# ECE411_Haptic_Compass.net
KiCad netlist of a schematic drawn in EAGLE
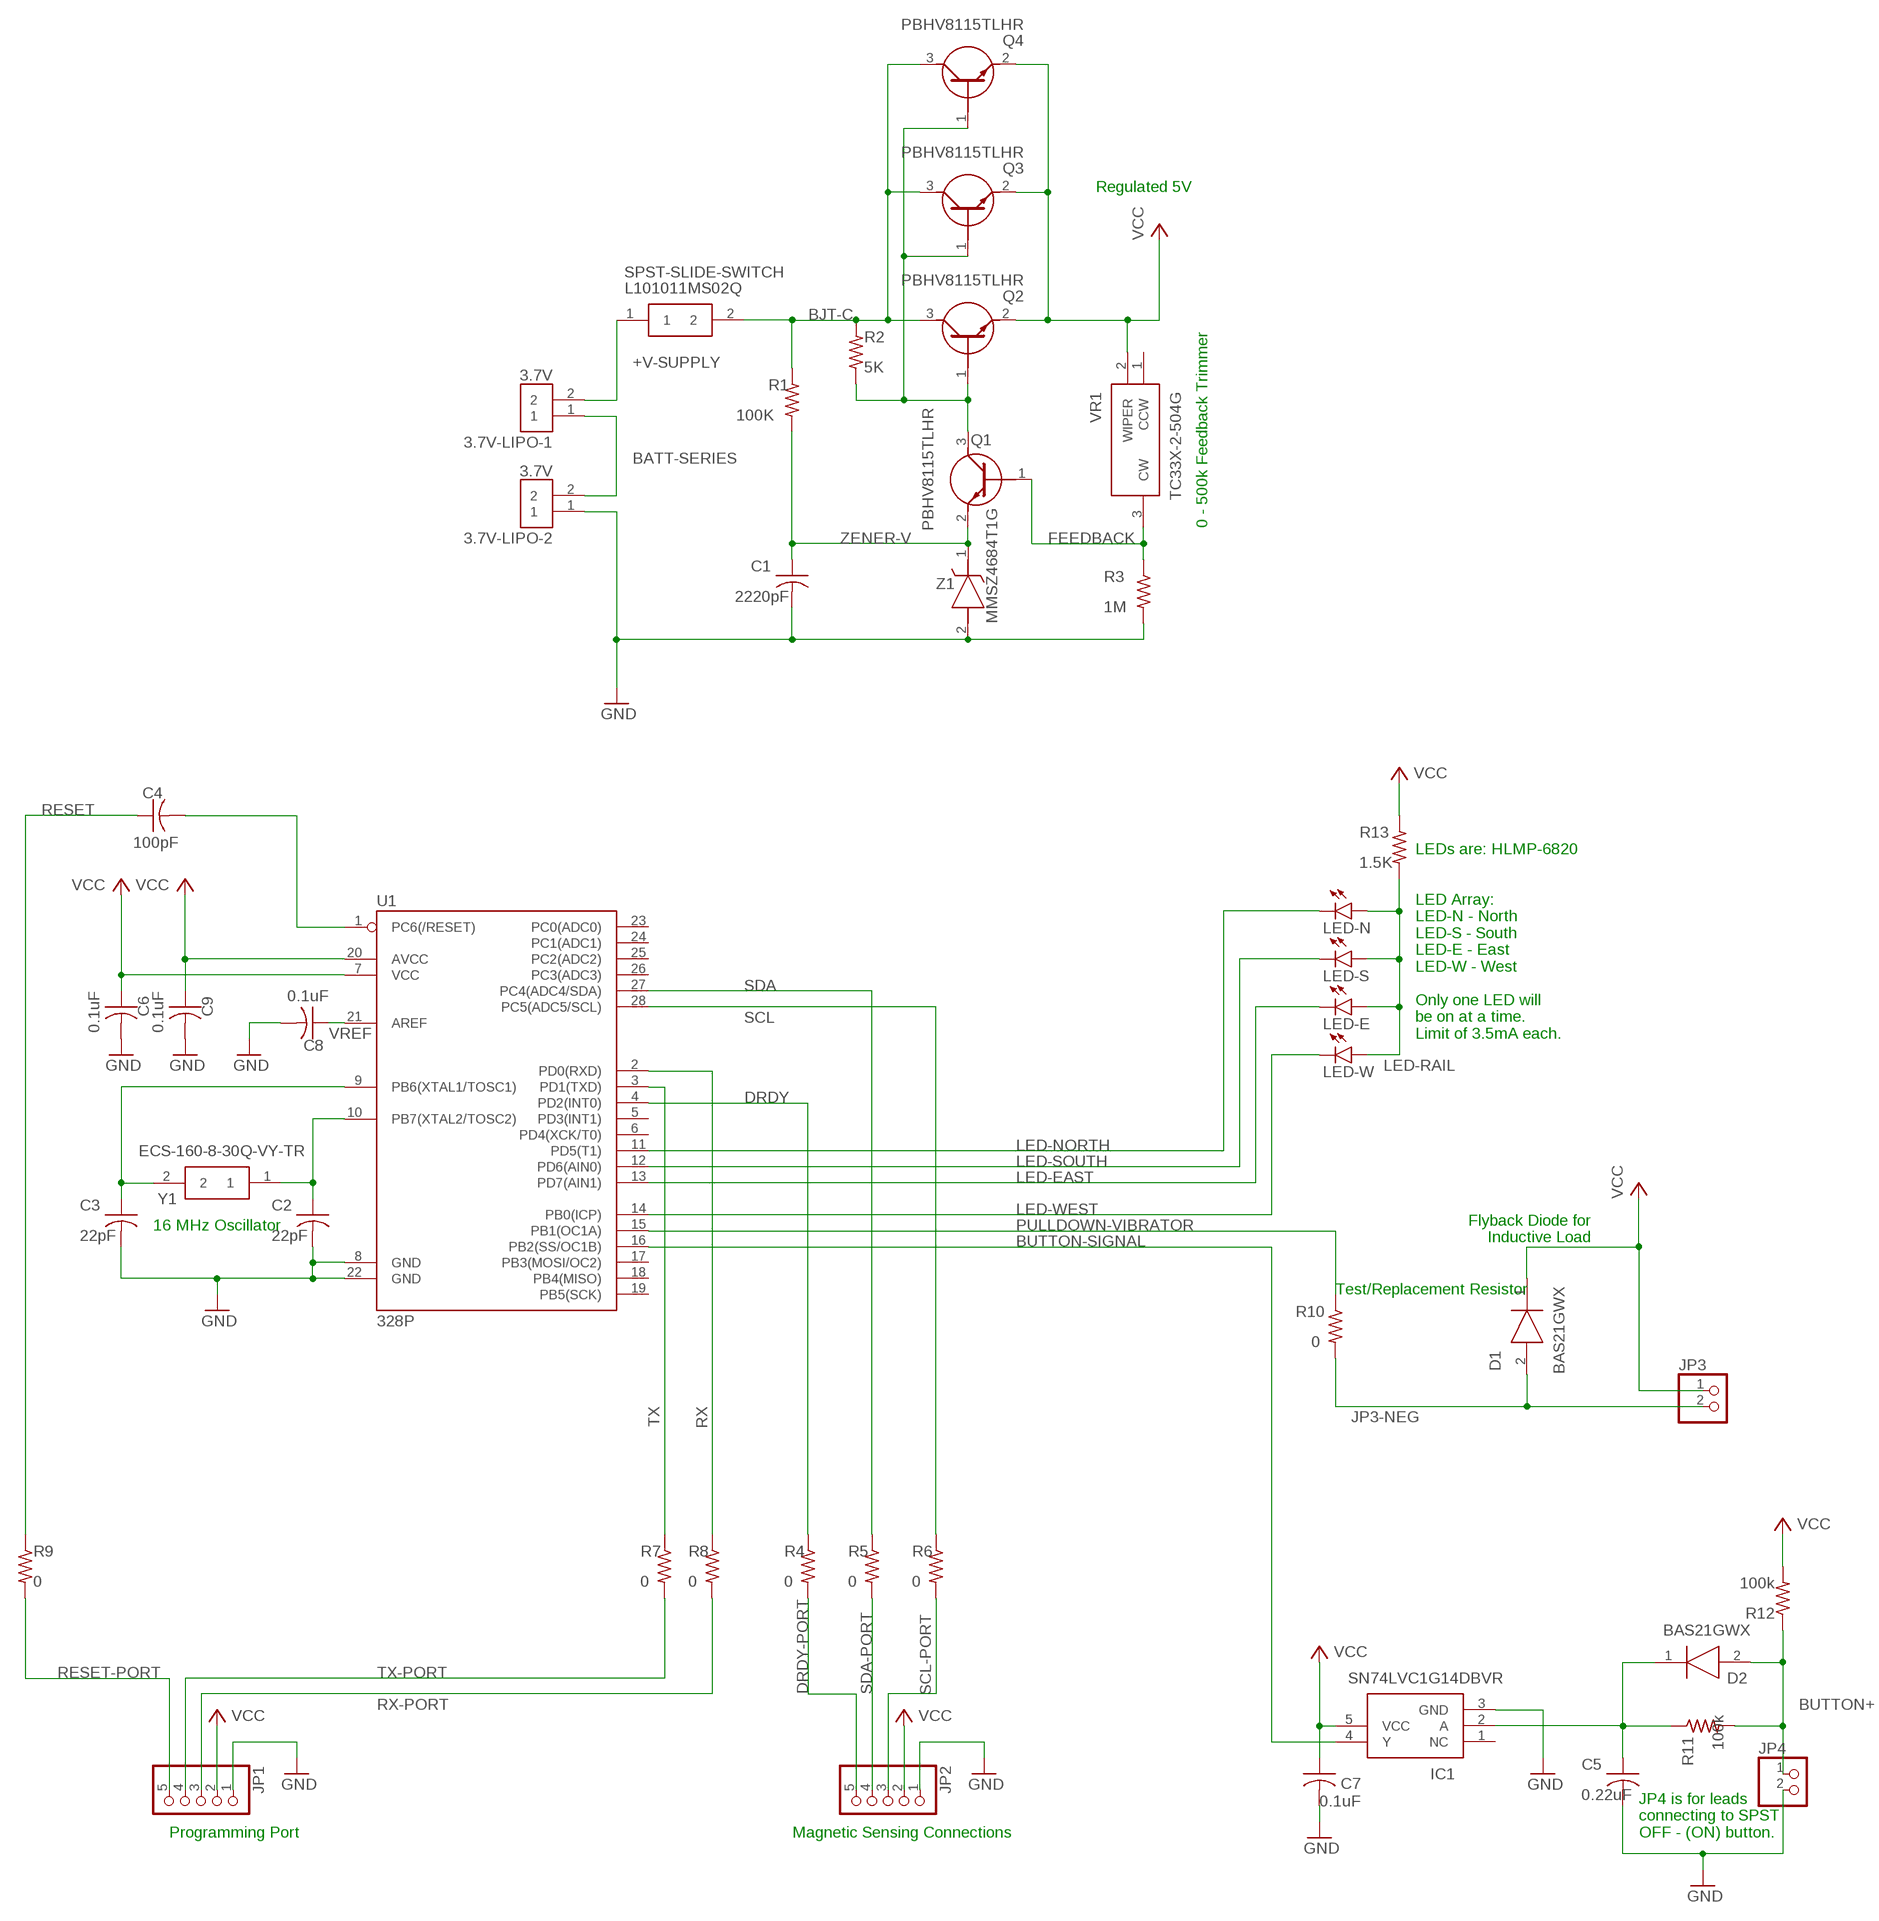
[diagram p0: schematic, sheet 1]

(export (version "E")
  (design (tool "Eeschema 10.0.6"))
  (components
    (comp (ref "3.7V-LIPO-1")
      (value "3.7V")
      (footprint "eagle-import:JST_S2B-PH-K-S(LF)(SN)")
      (fields
        (field (name "DIGI-KEY_PART_NUMBER") "455-1719-ND")
        (field (name "MF") "JST Sales")
        (field (name "MP") "S2B-PH-K-S_LF__SN_")
      )
      (libsource (lib "eagle-import") (part "S2B-PH-K-S(LF)(SN)"))
    )
    (comp (ref "3.7V-LIPO-2")
      (value "3.7V")
      (footprint "eagle-import:JST_S2B-PH-K-S(LF)(SN)")
      (fields
        (field (name "DIGI-KEY_PART_NUMBER") "455-1719-ND")
        (field (name "MF") "JST Sales")
        (field (name "MP") "S2B-PH-K-S_LF__SN_")
      )
      (libsource (lib "eagle-import") (part "S2B-PH-K-S(LF)(SN)"))
    )
    (comp (ref "C1")
      (value "2220pF")
      (footprint "eagle-import:C0805")
      (libsource (lib "eagle-import") (part "C-USC0805"))
    )
    (comp (ref "C2")
      (value "22pF")
      (footprint "eagle-import:C0805")
      (libsource (lib "eagle-import") (part "C-USC0805"))
    )
    (comp (ref "C3")
      (value "22pF")
      (footprint "eagle-import:C0805")
      (libsource (lib "eagle-import") (part "C-USC0805"))
    )
    (comp (ref "C4")
      (value "100pF")
      (footprint "eagle-import:C0805")
      (libsource (lib "eagle-import") (part "C-USC0805"))
    )
    (comp (ref "C5")
      (value "0.22uF")
      (footprint "eagle-import:C0805")
      (libsource (lib "eagle-import") (part "C-USC0805"))
    )
    (comp (ref "C6")
      (value "0.1uF")
      (footprint "eagle-import:C0805")
      (libsource (lib "eagle-import") (part "C-USC0805"))
    )
    (comp (ref "C7")
      (value "0.1uF")
      (footprint "eagle-import:C0805")
      (libsource (lib "eagle-import") (part "C-USC0805"))
    )
    (comp (ref "C8")
      (value "0.1uF")
      (footprint "eagle-import:C0805")
      (libsource (lib "eagle-import") (part "C-USC0805"))
    )
    (comp (ref "C9")
      (value "0.1uF")
      (footprint "eagle-import:C0805")
      (libsource (lib "eagle-import") (part "C-USC0805"))
    )
    (comp (ref "D1")
      (value "BAS21GWX")
      (footprint "eagle-import:SOD3616X130N")
      (fields (field (name "MOUSER_PART_NUMBER") "841-BAS21GWX"))
      (libsource (lib "eagle-import") (part "BAS21GWX"))
    )
    (comp (ref "D2")
      (value "BAS21GWX")
      (footprint "eagle-import:SOD3616X130N")
      (fields (field (name "MOUSER_PART_NUMBER") "841-BAS21GWX"))
      (libsource (lib "eagle-import") (part "BAS21GWX"))
    )
    (comp (ref "IC1")
      (value "SN74LVC1G14DBVR")
      (footprint "eagle-import:SOT95P280X145-5N")
      (fields (field (name "MOUSER_PART_NUMBER") "595-SN74LVC1G14DBVR"))
      (libsource (lib "eagle-import") (part "SN74LVC1G14DBVR"))
    )
    (comp (ref "JP1")
      (value "PINHD-1X5")
      (footprint "eagle-import:1X05")
      (libsource (lib "eagle-import") (part "PINHD-1X5"))
    )
    (comp (ref "JP2")
      (value "PINHD-1X5")
      (footprint "eagle-import:1X05")
      (libsource (lib "eagle-import") (part "PINHD-1X5"))
    )
    (comp (ref "JP3")
      (value "PINHD-1X2")
      (footprint "eagle-import:1X02")
      (libsource (lib "eagle-import") (part "PINHD-1X2"))
    )
    (comp (ref "JP4")
      (value "PINHD-1X2")
      (footprint "eagle-import:1X02")
      (libsource (lib "eagle-import") (part "PINHD-1X2"))
    )
    (comp (ref "LED-E")
      (value "LED5MM")
      (footprint "eagle-import:LED5MM")
      (libsource (lib "eagle-import") (part "LED5MM"))
    )
    (comp (ref "LED-N")
      (value "LED5MM")
      (footprint "eagle-import:LED5MM")
      (libsource (lib "eagle-import") (part "LED5MM"))
    )
    (comp (ref "LED-S")
      (value "LED5MM")
      (footprint "eagle-import:LED5MM")
      (libsource (lib "eagle-import") (part "LED5MM"))
    )
    (comp (ref "LED-W")
      (value "LED5MM")
      (footprint "eagle-import:LED5MM")
      (libsource (lib "eagle-import") (part "LED5MM"))
    )
    (comp (ref "Q1")
      (value "PBHV8115TLHR")
      (footprint "eagle-import:SOT95P230X110-3N")
      (fields (field (name "MOUSER_PART_NUMBER") "771-PBHV8115TLHR"))
      (libsource (lib "eagle-import") (part "PBHV8115TLHR"))
    )
    (comp (ref "Q2")
      (value "PBHV8115TLHR")
      (footprint "eagle-import:SOT95P230X110-3N")
      (fields (field (name "MOUSER_PART_NUMBER") "771-PBHV8115TLHR"))
      (libsource (lib "eagle-import") (part "PBHV8115TLHR"))
    )
    (comp (ref "Q3")
      (value "PBHV8115TLHR")
      (footprint "eagle-import:SOT95P230X110-3N")
      (fields (field (name "MOUSER_PART_NUMBER") "771-PBHV8115TLHR"))
      (libsource (lib "eagle-import") (part "PBHV8115TLHR"))
    )
    (comp (ref "Q4")
      (value "PBHV8115TLHR")
      (footprint "eagle-import:SOT95P230X110-3N")
      (fields (field (name "MOUSER_PART_NUMBER") "771-PBHV8115TLHR"))
      (libsource (lib "eagle-import") (part "PBHV8115TLHR"))
    )
    (comp (ref "R1")
      (value "100K")
      (footprint "eagle-import:R0805")
      (libsource (lib "eagle-import") (part "R-US_R0805"))
    )
    (comp (ref "R2")
      (value "5K")
      (footprint "eagle-import:R0805")
      (libsource (lib "eagle-import") (part "R-US_R0805"))
    )
    (comp (ref "R3")
      (value "1M")
      (footprint "eagle-import:R0805")
      (libsource (lib "eagle-import") (part "R-US_R0805"))
    )
    (comp (ref "R4")
      (value "0")
      (footprint "eagle-import:R0805")
      (libsource (lib "eagle-import") (part "R-US_R0805"))
    )
    (comp (ref "R5")
      (value "0")
      (footprint "eagle-import:R0805")
      (libsource (lib "eagle-import") (part "R-US_R0805"))
    )
    (comp (ref "R6")
      (value "0")
      (footprint "eagle-import:R0805")
      (libsource (lib "eagle-import") (part "R-US_R0805"))
    )
    (comp (ref "R7")
      (value "0")
      (footprint "eagle-import:R0805")
      (libsource (lib "eagle-import") (part "R-US_R0805"))
    )
    (comp (ref "R8")
      (value "0")
      (footprint "eagle-import:R0805")
      (libsource (lib "eagle-import") (part "R-US_R0805"))
    )
    (comp (ref "R9")
      (value "0")
      (footprint "eagle-import:R0805")
      (libsource (lib "eagle-import") (part "R-US_R0805"))
    )
    (comp (ref "R10")
      (value "0")
      (footprint "eagle-import:R0805")
      (libsource (lib "eagle-import") (part "R-US_R0805"))
    )
    (comp (ref "R11")
      (value "100k")
      (footprint "eagle-import:R0805")
      (libsource (lib "eagle-import") (part "R-US_R0805"))
    )
    (comp (ref "R12")
      (value "100k")
      (footprint "eagle-import:R0805")
      (libsource (lib "eagle-import") (part "R-US_R0805"))
    )
    (comp (ref "R13")
      (value "1.5K")
      (footprint "eagle-import:R0805")
      (libsource (lib "eagle-import") (part "R-US_R0805"))
    )
    (comp (ref "SPST-SLIDE-SWITCH")
      (value "L101011MS02Q")
      (footprint "eagle-import:CKC5106-ND")
      (fields (field (name "MOUSER_PART_NUMBER") "611-L101011MS02Q"))
      (libsource (lib "eagle-import") (part "L101011MS02Q"))
    )
    (comp (ref "U1")
      (value "328P")
      (footprint "eagle-import:DIP28")
      (libsource (lib "eagle-import") (part "ATMEGA328P_PDIP"))
    )
    (comp (ref "VR1")
      (value "TC33X-2-504G")
      (footprint "eagle-import:TC33X-2_1")
      (fields (field (name "MOUSER_PART_NUMBER") "652-TC33X-2-504G"))
      (libsource (lib "eagle-import") (part "TC33X-2-504G"))
    )
    (comp (ref "Y1")
      (value "ECS-160-8-30Q-VY-TR")
      (footprint "eagle-import:ECS80830QVSTR")
      (fields (field (name "MOUSER_PART_NUMBER") "520-160-8-30Q-VYT"))
      (libsource (lib "eagle-import") (part "ECS-160-8-30Q-VY-TR"))
    )
    (comp (ref "Z1")
      (value "MMSZ4684T1G")
      (footprint "eagle-import:SOD3716X135N")
      (fields (field (name "MOUSER_PART_NUMBER") "863-MMSZ4684T1G"))
      (libsource (lib "eagle-import") (part "MMSZ4684T1G"))
    )
  )
  (nets
    (net (code "1") (name "/+V-SUPPLY") (class "Default")
      (node (ref "3.7V-LIPO-1") (pin "2") (pinfunction "2_2") (pintype "passive"))
      (node (ref "SPST-SLIDE-SWITCH") (pin "1") (pinfunction "1_1") (pintype "bidirectional"))
    )
    (net (code "2") (name "/BATT-SERIES") (class "Default")
      (node (ref "3.7V-LIPO-1") (pin "1") (pinfunction "1_1") (pintype "passive"))
      (node (ref "3.7V-LIPO-2") (pin "2") (pinfunction "2_2") (pintype "passive"))
    )
    (net (code "3") (name "/BJT-C") (class "Default")
      (node (ref "Q2") (pin "3") (pinfunction "C_3") (pintype "bidirectional"))
      (node (ref "Q3") (pin "3") (pinfunction "C_3") (pintype "bidirectional"))
      (node (ref "Q4") (pin "3") (pinfunction "C_3") (pintype "bidirectional"))
      (node (ref "R1") (pin "1") (pinfunction "1_1") (pintype "passive"))
      (node (ref "R2") (pin "1") (pinfunction "1_1") (pintype "passive"))
      (node (ref "SPST-SLIDE-SWITCH") (pin "2") (pinfunction "2_2") (pintype "bidirectional"))
    )
    (net (code "4") (name "/BUTTON+") (class "Default")
      (node (ref "D2") (pin "2") (pinfunction "A_2") (pintype "bidirectional"))
      (node (ref "JP4") (pin "1") (pinfunction "1_1") (pintype "passive"))
      (node (ref "R11") (pin "2") (pinfunction "2_2") (pintype "passive"))
      (node (ref "R12") (pin "1") (pinfunction "1_1") (pintype "passive"))
    )
    (net (code "5") (name "/BUTTON-SIGNAL") (class "Default")
      (node (ref "IC1") (pin "4") (pinfunction "Y_4") (pintype "bidirectional"))
      (node (ref "U1") (pin "16") (pinfunction "PB2(SS/OC1B)_16") (pintype "bidirectional"))
    )
    (net (code "6") (name "/DRDY") (class "Default")
      (node (ref "R4") (pin "1") (pinfunction "1_1") (pintype "passive"))
      (node (ref "U1") (pin "4") (pinfunction "PD2(INT0)_4") (pintype "bidirectional"))
    )
    (net (code "7") (name "/DRDY-PORT") (class "Default")
      (node (ref "JP2") (pin "5") (pinfunction "5_5") (pintype "passive"))
      (node (ref "R4") (pin "2") (pinfunction "2_2") (pintype "passive"))
    )
    (net (code "8") (name "/FEEDBACK") (class "Default")
      (node (ref "Q1") (pin "1") (pinfunction "B_1") (pintype "bidirectional"))
      (node (ref "R3") (pin "1") (pinfunction "1_1") (pintype "passive"))
      (node (ref "VR1") (pin "3") (pinfunction "CW_3") (pintype "bidirectional"))
    )
    (net (code "9") (name "/JP3-NEG") (class "Default")
      (node (ref "D1") (pin "2") (pinfunction "A_2") (pintype "bidirectional"))
      (node (ref "JP3") (pin "2") (pinfunction "2_2") (pintype "passive"))
      (node (ref "R10") (pin "2") (pinfunction "2_2") (pintype "passive"))
    )
    (net (code "10") (name "/LED-EAST") (class "Default")
      (node (ref "LED-E") (pin "K") (pinfunction "C_K") (pintype "passive"))
      (node (ref "U1") (pin "13") (pinfunction "PD7(AIN1)_13") (pintype "bidirectional"))
    )
    (net (code "11") (name "/LED-NORTH") (class "Default")
      (node (ref "LED-N") (pin "K") (pinfunction "C_K") (pintype "passive"))
      (node (ref "U1") (pin "11") (pinfunction "PD5(T1)_11") (pintype "bidirectional"))
    )
    (net (code "12") (name "/LED-RAIL") (class "Default")
      (node (ref "LED-E") (pin "A") (pinfunction "A_A") (pintype "passive"))
      (node (ref "LED-N") (pin "A") (pinfunction "A_A") (pintype "passive"))
      (node (ref "LED-S") (pin "A") (pinfunction "A_A") (pintype "passive"))
      (node (ref "LED-W") (pin "A") (pinfunction "A_A") (pintype "passive"))
      (node (ref "R13") (pin "2") (pinfunction "2_2") (pintype "passive"))
    )
    (net (code "13") (name "/LED-SOUTH") (class "Default")
      (node (ref "LED-S") (pin "K") (pinfunction "C_K") (pintype "passive"))
      (node (ref "U1") (pin "12") (pinfunction "PD6(AIN0)_12") (pintype "bidirectional"))
    )
    (net (code "14") (name "/LED-WEST") (class "Default")
      (node (ref "LED-W") (pin "K") (pinfunction "C_K") (pintype "passive"))
      (node (ref "U1") (pin "14") (pinfunction "PB0(ICP)_14") (pintype "bidirectional"))
    )
    (net (code "15") (name "/PULLDOWN-VIBRATOR") (class "Default")
      (node (ref "R10") (pin "1") (pinfunction "1_1") (pintype "passive"))
      (node (ref "U1") (pin "15") (pinfunction "PB1(OC1A)_15") (pintype "bidirectional"))
    )
    (net (code "16") (name "/RESET") (class "Default")
      (node (ref "C4") (pin "1") (pinfunction "1_1") (pintype "passive"))
      (node (ref "R9") (pin "1") (pinfunction "1_1") (pintype "passive"))
    )
    (net (code "17") (name "/RESET-PORT") (class "Default")
      (node (ref "JP1") (pin "5") (pinfunction "5_5") (pintype "passive"))
      (node (ref "R9") (pin "2") (pinfunction "2_2") (pintype "passive"))
    )
    (net (code "18") (name "/RX") (class "Default")
      (node (ref "R8") (pin "1") (pinfunction "1_1") (pintype "passive"))
      (node (ref "U1") (pin "2") (pinfunction "PD0(RXD)_2") (pintype "bidirectional"))
    )
    (net (code "19") (name "/RX-PORT") (class "Default")
      (node (ref "JP1") (pin "3") (pinfunction "3_3") (pintype "passive"))
      (node (ref "R8") (pin "2") (pinfunction "2_2") (pintype "passive"))
    )
    (net (code "20") (name "/SCL") (class "Default")
      (node (ref "R6") (pin "1") (pinfunction "1_1") (pintype "passive"))
      (node (ref "U1") (pin "28") (pinfunction "PC5(ADC5/SCL)_28") (pintype "bidirectional"))
    )
    (net (code "21") (name "/SCL-PORT") (class "Default")
      (node (ref "JP2") (pin "3") (pinfunction "3_3") (pintype "passive"))
      (node (ref "R6") (pin "2") (pinfunction "2_2") (pintype "passive"))
    )
    (net (code "22") (name "/SDA") (class "Default")
      (node (ref "R5") (pin "1") (pinfunction "1_1") (pintype "passive"))
      (node (ref "U1") (pin "27") (pinfunction "PC4(ADC4/SDA)_27") (pintype "bidirectional"))
    )
    (net (code "23") (name "/SDA-PORT") (class "Default")
      (node (ref "JP2") (pin "4") (pinfunction "4_4") (pintype "passive"))
      (node (ref "R5") (pin "2") (pinfunction "2_2") (pintype "passive"))
    )
    (net (code "24") (name "/TX") (class "Default")
      (node (ref "R7") (pin "1") (pinfunction "1_1") (pintype "passive"))
      (node (ref "U1") (pin "3") (pinfunction "PD1(TXD)_3") (pintype "bidirectional"))
    )
    (net (code "25") (name "/TX-PORT") (class "Default")
      (node (ref "JP1") (pin "4") (pinfunction "4_4") (pintype "passive"))
      (node (ref "R7") (pin "2") (pinfunction "2_2") (pintype "passive"))
    )
    (net (code "26") (name "/VREF") (class "Default")
      (node (ref "C8") (pin "1") (pinfunction "1_1") (pintype "passive"))
      (node (ref "U1") (pin "21") (pinfunction "AREF_21") (pintype "bidirectional"))
    )
    (net (code "27") (name "/ZENER-V") (class "Default")
      (node (ref "C1") (pin "1") (pinfunction "1_1") (pintype "passive"))
      (node (ref "Q1") (pin "2") (pinfunction "E_2") (pintype "bidirectional"))
      (node (ref "R1") (pin "2") (pinfunction "2_2") (pintype "passive"))
      (node (ref "Z1") (pin "1") (pinfunction "K_1") (pintype "bidirectional"))
    )
    (net (code "28") (name "GND") (class "Default")
      (node (ref "3.7V-LIPO-2") (pin "1") (pinfunction "1_1") (pintype "passive"))
      (node (ref "C1") (pin "2") (pinfunction "2_2") (pintype "passive"))
      (node (ref "C2") (pin "2") (pinfunction "2_2") (pintype "passive"))
      (node (ref "C3") (pin "2") (pinfunction "2_2") (pintype "passive"))
      (node (ref "C5") (pin "2") (pinfunction "2_2") (pintype "passive"))
      (node (ref "C6") (pin "2") (pinfunction "2_2") (pintype "passive"))
      (node (ref "C7") (pin "2") (pinfunction "2_2") (pintype "passive"))
      (node (ref "C8") (pin "2") (pinfunction "2_2") (pintype "passive"))
      (node (ref "C9") (pin "2") (pinfunction "2_2") (pintype "passive"))
      (node (ref "IC1") (pin "3") (pinfunction "GND_3") (pintype "bidirectional"))
      (node (ref "JP1") (pin "1") (pinfunction "1_1") (pintype "passive"))
      (node (ref "JP2") (pin "1") (pinfunction "1_1") (pintype "passive"))
      (node (ref "JP4") (pin "2") (pinfunction "2_2") (pintype "passive"))
      (node (ref "R3") (pin "2") (pinfunction "2_2") (pintype "passive"))
      (node (ref "U1") (pin "22") (pinfunction "GND_22") (pintype "bidirectional"))
      (node (ref "U1") (pin "8") (pinfunction "GND_8") (pintype "bidirectional"))
      (node (ref "Z1") (pin "2") (pinfunction "A_2") (pintype "bidirectional"))
    )
    (net (code "29") (name "Net-(D2-K)") (class "Default")
      (node (ref "C5") (pin "1") (pinfunction "1_1") (pintype "passive"))
      (node (ref "D2") (pin "1") (pinfunction "K_1") (pintype "bidirectional"))
      (node (ref "IC1") (pin "2") (pinfunction "A_2") (pintype "bidirectional"))
      (node (ref "R11") (pin "1") (pinfunction "1_1") (pintype "passive"))
    )
    (net (code "30") (name "Net-(Q1-C)") (class "Default")
      (node (ref "Q1") (pin "3") (pinfunction "C_3") (pintype "bidirectional"))
      (node (ref "Q2") (pin "1") (pinfunction "B_1") (pintype "bidirectional"))
      (node (ref "Q3") (pin "1") (pinfunction "B_1") (pintype "bidirectional"))
      (node (ref "Q4") (pin "1") (pinfunction "B_1") (pintype "bidirectional"))
      (node (ref "R2") (pin "2") (pinfunction "2_2") (pintype "passive"))
    )
    (net (code "31") (name "Net-(U1-PB6(XTAL1{slash}TOSC1))") (class "Default")
      (node (ref "C3") (pin "1") (pinfunction "1_1") (pintype "passive"))
      (node (ref "U1") (pin "9") (pinfunction "PB6(XTAL1/TOSC1)_9") (pintype "bidirectional"))
      (node (ref "Y1") (pin "2") (pinfunction "2_2") (pintype "bidirectional"))
    )
    (net (code "32") (name "Net-(U1-PB7(XTAL2{slash}TOSC2))") (class "Default")
      (node (ref "C2") (pin "1") (pinfunction "1_1") (pintype "passive"))
      (node (ref "U1") (pin "10") (pinfunction "PB7(XTAL2/TOSC2)_10") (pintype "bidirectional"))
      (node (ref "Y1") (pin "1") (pinfunction "1_1") (pintype "bidirectional"))
    )
    (net (code "33") (name "Net-(U1-PC6({slash}RESET))") (class "Default")
      (node (ref "C4") (pin "2") (pinfunction "2_2") (pintype "passive"))
      (node (ref "U1") (pin "1") (pinfunction "PC6(/RESET)_1") (pintype "bidirectional"))
    )
    (net (code "34") (name "VCC") (class "Default")
      (node (ref "C6") (pin "1") (pinfunction "1_1") (pintype "passive"))
      (node (ref "C7") (pin "1") (pinfunction "1_1") (pintype "passive"))
      (node (ref "C9") (pin "1") (pinfunction "1_1") (pintype "passive"))
      (node (ref "D1") (pin "1") (pinfunction "K_1") (pintype "bidirectional"))
      (node (ref "IC1") (pin "5") (pinfunction "VCC_5") (pintype "bidirectional"))
      (node (ref "JP1") (pin "2") (pinfunction "2_2") (pintype "passive"))
      (node (ref "JP2") (pin "2") (pinfunction "2_2") (pintype "passive"))
      (node (ref "JP3") (pin "1") (pinfunction "1_1") (pintype "passive"))
      (node (ref "Q2") (pin "2") (pinfunction "E_2") (pintype "bidirectional"))
      (node (ref "Q3") (pin "2") (pinfunction "E_2") (pintype "bidirectional"))
      (node (ref "Q4") (pin "2") (pinfunction "E_2") (pintype "bidirectional"))
      (node (ref "R12") (pin "2") (pinfunction "2_2") (pintype "passive"))
      (node (ref "R13") (pin "1") (pinfunction "1_1") (pintype "passive"))
      (node (ref "U1") (pin "20") (pinfunction "AVCC_20") (pintype "bidirectional"))
      (node (ref "U1") (pin "7") (pinfunction "VCC_7") (pintype "bidirectional"))
      (node (ref "VR1") (pin "2") (pinfunction "WIPER_2") (pintype "bidirectional"))
    )
    (net (code "35") (name "unconnected-(IC1-NC-Pad1)") (class "Default")
      (node (ref "IC1") (pin "1") (pinfunction "NC_1") (pintype "no_connect"))
    )
    (net (code "36") (name "unconnected-(U1-PB3(MOSI{slash}OC2)-Pad17)") (class "Default")
      (node (ref "U1") (pin "17") (pinfunction "PB3(MOSI/OC2)_17") (pintype "bidirectional"))
    )
    (net (code "37") (name "unconnected-(U1-PB4(MISO)-Pad18)") (class "Default")
      (node (ref "U1") (pin "18") (pinfunction "PB4(MISO)_18") (pintype "bidirectional"))
    )
    (net (code "38") (name "unconnected-(U1-PB5(SCK)-Pad19)") (class "Default")
      (node (ref "U1") (pin "19") (pinfunction "PB5(SCK)_19") (pintype "bidirectional"))
    )
    (net (code "39") (name "unconnected-(U1-PC0(ADC0)-Pad23)") (class "Default")
      (node (ref "U1") (pin "23") (pinfunction "PC0(ADC0)_23") (pintype "bidirectional"))
    )
    (net (code "40") (name "unconnected-(U1-PC1(ADC1)-Pad24)") (class "Default")
      (node (ref "U1") (pin "24") (pinfunction "PC1(ADC1)_24") (pintype "bidirectional"))
    )
    (net (code "41") (name "unconnected-(U1-PC2(ADC2)-Pad25)") (class "Default")
      (node (ref "U1") (pin "25") (pinfunction "PC2(ADC2)_25") (pintype "bidirectional"))
    )
    (net (code "42") (name "unconnected-(U1-PC3(ADC3)-Pad26)") (class "Default")
      (node (ref "U1") (pin "26") (pinfunction "PC3(ADC3)_26") (pintype "bidirectional"))
    )
    (net (code "43") (name "unconnected-(U1-PD3(INT1)-Pad5)") (class "Default")
      (node (ref "U1") (pin "5") (pinfunction "PD3(INT1)_5") (pintype "bidirectional"))
    )
    (net (code "44") (name "unconnected-(U1-PD4(XCK{slash}T0)-Pad6)") (class "Default")
      (node (ref "U1") (pin "6") (pinfunction "PD4(XCK/T0)_6") (pintype "bidirectional"))
    )
    (net (code "45") (name "unconnected-(VR1-CCW-Pad1)") (class "Default")
      (node (ref "VR1") (pin "1") (pinfunction "CCW_1") (pintype "bidirectional"))
    )
  )
)
